# top.net
KiCad netlist of a schematic drawn in EAGLE
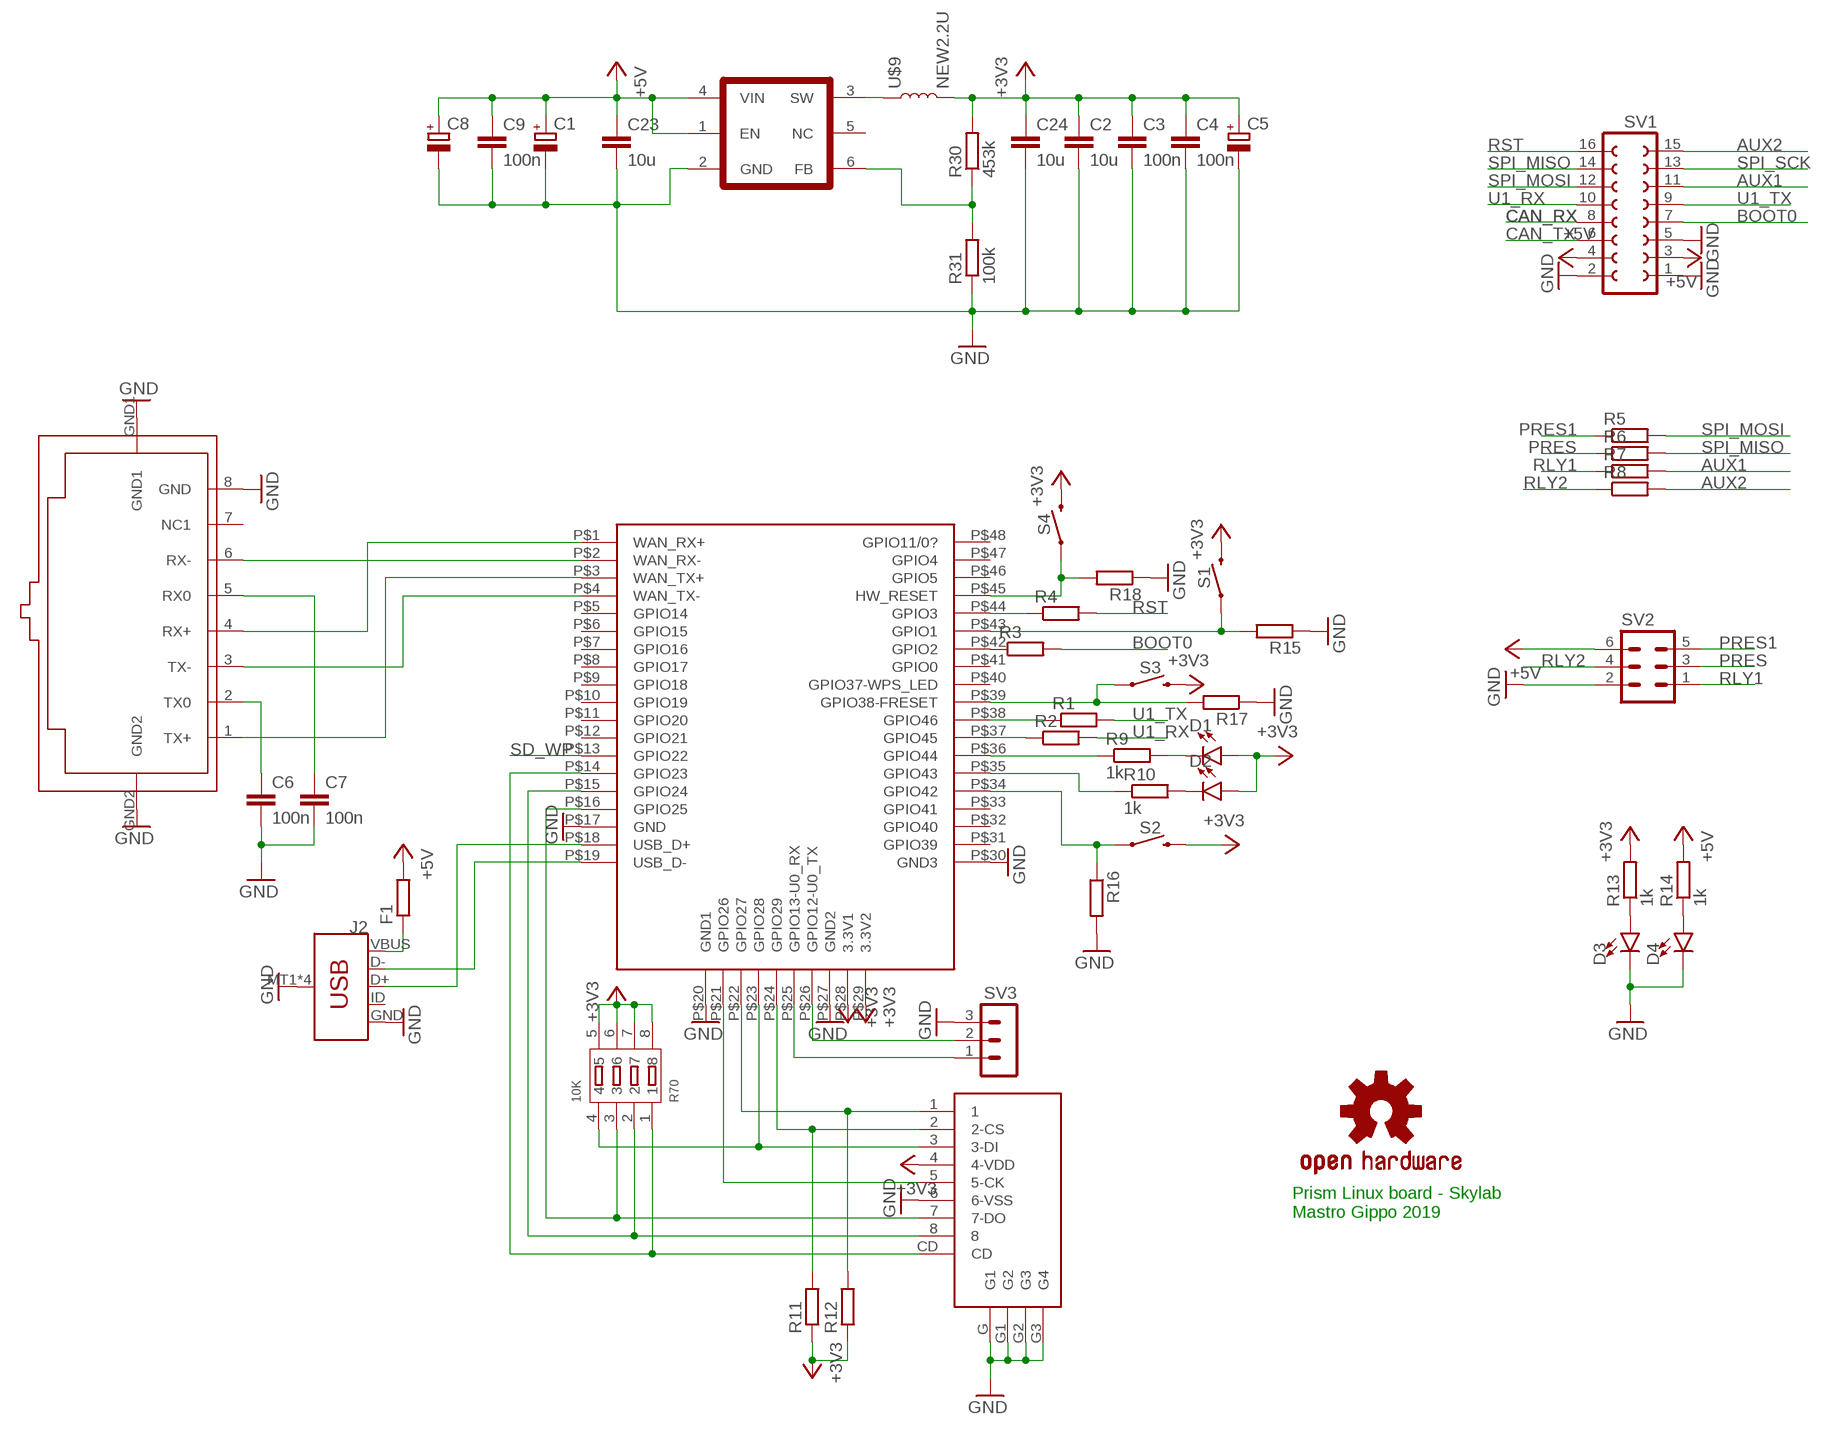
[diagram p0: schematic, sheet 1]

(export (version "E")
  (design (tool "Eeschema 10.0.6"))
  (components
    (comp (ref "C1")
      (value "CPOL-EUB/3528-21R")
      (footprint "eagle-import:B_3528-21R")
      (libsource (lib "eagle-import") (part "CPOL-EUB/3528-21R"))
    )
    (comp (ref "C2")
      (value "10u")
      (footprint "eagle-import:C0805K")
      (libsource (lib "eagle-import") (part "C-EUC0805K"))
    )
    (comp (ref "C3")
      (value "100n")
      (footprint "eagle-import:C0805K")
      (libsource (lib "eagle-import") (part "C-EUC0805K"))
    )
    (comp (ref "C4")
      (value "100n")
      (footprint "eagle-import:C0805K")
      (libsource (lib "eagle-import") (part "C-EUC0805K"))
    )
    (comp (ref "C5")
      (value "CPOL-EUB/3528-21R")
      (footprint "eagle-import:B_3528-21R")
      (libsource (lib "eagle-import") (part "CPOL-EUB/3528-21R"))
    )
    (comp (ref "C6")
      (value "100n")
      (footprint "eagle-import:C0805K")
      (libsource (lib "eagle-import") (part "C-EUC0805K"))
    )
    (comp (ref "C7")
      (value "100n")
      (footprint "eagle-import:C0805K")
      (libsource (lib "eagle-import") (part "C-EUC0805K"))
    )
    (comp (ref "C8")
      (value "CPOL-EUB/3528-21R")
      (footprint "eagle-import:B_3528-21R")
      (libsource (lib "eagle-import") (part "CPOL-EUB/3528-21R"))
    )
    (comp (ref "C9")
      (value "100n")
      (footprint "eagle-import:C0805K")
      (libsource (lib "eagle-import") (part "C-EUC0805K"))
    )
    (comp (ref "C23")
      (value "10u")
      (footprint "eagle-import:C0805K")
      (libsource (lib "eagle-import") (part "C-EUC0805K"))
    )
    (comp (ref "C24")
      (value "10u")
      (footprint "eagle-import:C0805K")
      (libsource (lib "eagle-import") (part "C-EUC0805K"))
    )
    (comp (ref "D1")
      (value "LED3MM")
      (footprint "eagle-import:LED_3MM")
      (libsource (lib "eagle-import") (part "LED3MM"))
    )
    (comp (ref "D2")
      (value "LED3MM")
      (footprint "eagle-import:LED_3MM")
      (libsource (lib "eagle-import") (part "LED3MM"))
    )
    (comp (ref "D3")
      (value "LED1206")
      (footprint "eagle-import:LED-1206")
      (libsource (lib "eagle-import") (part "LED1206"))
    )
    (comp (ref "D4")
      (value "LED1206")
      (footprint "eagle-import:LED-1206")
      (libsource (lib "eagle-import") (part "LED1206"))
    )
    (comp (ref "F1")
      (value "R-EU_R0603")
      (footprint "eagle-import:R0603")
      (libsource (lib "eagle-import") (part "R-EU_R0603"))
    )
    (comp (ref "J2")
      (value "USB_MICRO-B_SMT")
      (footprint "eagle-import:USB-MICROB")
      (libsource (lib "eagle-import") (part "USB_MICRO-B_SMT"))
    )
    (comp (ref "R1")
      (value "R-EU_R0805")
      (footprint "eagle-import:R0805")
      (libsource (lib "eagle-import") (part "R-EU_R0805"))
    )
    (comp (ref "R2")
      (value "R-EU_R0805")
      (footprint "eagle-import:R0805")
      (libsource (lib "eagle-import") (part "R-EU_R0805"))
    )
    (comp (ref "R3")
      (value "R-EU_R0805")
      (footprint "eagle-import:R0805")
      (libsource (lib "eagle-import") (part "R-EU_R0805"))
    )
    (comp (ref "R4")
      (value "R-EU_R0805")
      (footprint "eagle-import:R0805")
      (libsource (lib "eagle-import") (part "R-EU_R0805"))
    )
    (comp (ref "R5")
      (value "R-EU_R0805")
      (footprint "eagle-import:R0805")
      (libsource (lib "eagle-import") (part "R-EU_R0805"))
    )
    (comp (ref "R6")
      (value "R-EU_R0805")
      (footprint "eagle-import:R0805")
      (libsource (lib "eagle-import") (part "R-EU_R0805"))
    )
    (comp (ref "R7")
      (value "R-EU_R0805")
      (footprint "eagle-import:R0805")
      (libsource (lib "eagle-import") (part "R-EU_R0805"))
    )
    (comp (ref "R8")
      (value "R-EU_R0805")
      (footprint "eagle-import:R0805")
      (libsource (lib "eagle-import") (part "R-EU_R0805"))
    )
    (comp (ref "R9")
      (value "1k")
      (footprint "eagle-import:R0805")
      (libsource (lib "eagle-import") (part "R-EU_R0805"))
    )
    (comp (ref "R10")
      (value "1k")
      (footprint "eagle-import:R0805")
      (libsource (lib "eagle-import") (part "R-EU_R0805"))
    )
    (comp (ref "R11")
      (value "R-EU_R0805")
      (footprint "eagle-import:R0805")
      (libsource (lib "eagle-import") (part "R-EU_R0805"))
    )
    (comp (ref "R12")
      (value "R-EU_R0805")
      (footprint "eagle-import:R0805")
      (libsource (lib "eagle-import") (part "R-EU_R0805"))
    )
    (comp (ref "R13")
      (value "1k")
      (footprint "eagle-import:R0805")
      (libsource (lib "eagle-import") (part "R-EU_R0805"))
    )
    (comp (ref "R14")
      (value "1k")
      (footprint "eagle-import:R0805")
      (libsource (lib "eagle-import") (part "R-EU_R0805"))
    )
    (comp (ref "R15")
      (value "R-EU_R0805")
      (footprint "eagle-import:R0805")
      (libsource (lib "eagle-import") (part "R-EU_R0805"))
    )
    (comp (ref "R16")
      (value "R-EU_R0805")
      (footprint "eagle-import:R0805")
      (libsource (lib "eagle-import") (part "R-EU_R0805"))
    )
    (comp (ref "R17")
      (value "R-EU_R0805")
      (footprint "eagle-import:R0805")
      (libsource (lib "eagle-import") (part "R-EU_R0805"))
    )
    (comp (ref "R18")
      (value "R-EU_R0805")
      (footprint "eagle-import:R0805")
      (libsource (lib "eagle-import") (part "R-EU_R0805"))
    )
    (comp (ref "R30")
      (value "453k")
      (footprint "eagle-import:R0805")
      (libsource (lib "eagle-import") (part "R_EU"))
    )
    (comp (ref "R31")
      (value "100k")
      (footprint "eagle-import:R0805")
      (libsource (lib "eagle-import") (part "R_EU"))
    )
    (comp (ref "R70")
      (value "10K")
      (footprint "eagle-import:RA1206-8")
      (fields (field (name "MPN") "Chip-Array-Series-1%"))
      (libsource (lib "eagle-import") (part "SMD-RES-ARRAY-1K-4R(RA1206-8)"))
    )
    (comp (ref "S1")
      (value "MOMENTARY-SWITCH-SPST-SMD-6.0X3.5MM")
      (footprint "eagle-import:TACTILE_SWITCH_SMD_6.0X3.5MM")
      (libsource (lib "eagle-import") (part "MOMENTARY-SWITCH-SPST-SMD-6.0X3.5MM"))
    )
    (comp (ref "S2")
      (value "MOMENTARY-SWITCH-SPST-SMD-6.0X3.5MM")
      (footprint "eagle-import:TACTILE_SWITCH_SMD_6.0X3.5MM")
      (libsource (lib "eagle-import") (part "MOMENTARY-SWITCH-SPST-SMD-6.0X3.5MM"))
    )
    (comp (ref "S3")
      (value "MOMENTARY-SWITCH-SPST-PTH-RIGHT-ANGLE")
      (footprint "eagle-import:TACTILE_SWITCH_PTH_RIGHT_ANGLE")
      (libsource (lib "eagle-import") (part "MOMENTARY-SWITCH-SPST-PTH-RIGHT-ANGLE"))
    )
    (comp (ref "S4")
      (value "MOMENTARY-SWITCH-SPST-SMD-6.0X3.5MM")
      (footprint "eagle-import:TACTILE_SWITCH_SMD_6.0X3.5MM")
      (libsource (lib "eagle-import") (part "MOMENTARY-SWITCH-SPST-SMD-6.0X3.5MM"))
    )
    (comp (ref "SV1")
      (value "FE08-2")
      (footprint "eagle-import:FE08-2")
      (libsource (lib "eagle-import") (part "FE08-2"))
    )
    (comp (ref "SV2")
      (value "MA03-2")
      (footprint "eagle-import:MA03-2")
      (libsource (lib "eagle-import") (part "MA03-2"))
    )
    (comp (ref "SV3")
      (value "MA03-1")
      (footprint "eagle-import:MA03-1")
      (libsource (lib "eagle-import") (part "MA03-1"))
    )
    (comp (ref "U$1")
      (value "RJ45-TRAFO")
      (footprint "eagle-import:RJ45-TRAFO")
      (libsource (lib "eagle-import") (part "RJ45-TRAFO"))
    )
    (comp (ref "U$2")
      (value "SKW92B")
      (footprint "eagle-import:SKW92")
      (libsource (lib "eagle-import") (part "SKW92B"))
    )
    (comp (ref "U$3")
      (value "MICRO_SD")
      (footprint "eagle-import:MICRO_SD_C")
      (libsource (lib "eagle-import") (part "MICRO_SD"))
    )
    (comp (ref "U$4")
      (value "OSHW-LOGOS")
      (footprint "eagle-import:OSHW-LOGO-S")
      (libsource (lib "eagle-import") (part "OSHW-LOGOS"))
    )
    (comp (ref "U$8")
      (value "TLV62658")
      (footprint "eagle-import:SOT23-6")
      (libsource (lib "eagle-import") (part "TLV62658"))
    )
    (comp (ref "U$9")
      (value "NEW2.2U")
      (footprint "eagle-import:INDUCTOR_4X4MM")
      (libsource (lib "eagle-import") (part "NEW2.2U"))
    )
  )
  (nets
    (net (code "1") (name "+3V3") (class "Default")
      (node (ref "C2") (pin "1") (pinfunction "1_1") (pintype "passive"))
      (node (ref "C24") (pin "1") (pinfunction "1_1") (pintype "passive"))
      (node (ref "C3") (pin "1") (pinfunction "1_1") (pintype "passive"))
      (node (ref "C4") (pin "1") (pinfunction "1_1") (pintype "passive"))
      (node (ref "C5") (pin "+") (pinfunction "+_+") (pintype "passive"))
      (node (ref "D1") (pin "A") (pinfunction "A_A") (pintype "passive"))
      (node (ref "D2") (pin "A") (pinfunction "A_A") (pintype "passive"))
      (node (ref "R11") (pin "1") (pinfunction "1_1") (pintype "passive"))
      (node (ref "R12") (pin "1") (pinfunction "1_1") (pintype "passive"))
      (node (ref "R13") (pin "2") (pinfunction "2_2") (pintype "passive"))
      (node (ref "R30") (pin "2") (pinfunction "2_2") (pintype "passive"))
      (node (ref "R70") (pin "5") (pinfunction "5_5") (pintype "bidirectional"))
      (node (ref "R70") (pin "6") (pinfunction "6_6") (pintype "bidirectional"))
      (node (ref "R70") (pin "7") (pinfunction "7_7") (pintype "bidirectional"))
      (node (ref "R70") (pin "8") (pinfunction "8_8") (pintype "bidirectional"))
      (node (ref "S1") (pin "2") (pinfunction "2_2") (pintype "passive"))
      (node (ref "S2") (pin "2") (pinfunction "2_2") (pintype "passive"))
      (node (ref "S3") (pin "2") (pinfunction "2_2") (pintype "passive"))
      (node (ref "S4") (pin "2") (pinfunction "2_2") (pintype "passive"))
      (node (ref "U$2") (pin "P$28") (pinfunction "3.3V1_P$28") (pintype "bidirectional"))
      (node (ref "U$2") (pin "P$29") (pinfunction "3.3V2_P$29") (pintype "bidirectional"))
      (node (ref "U$3") (pin "4") (pinfunction "4-VDD_4") (pintype "bidirectional"))
      (node (ref "U$9") (pin "P$2") (pinfunction "2_P$2") (pintype "passive"))
    )
    (net (code "2") (name "+5V") (class "Default")
      (node (ref "C1") (pin "+") (pinfunction "+_+") (pintype "passive"))
      (node (ref "C23") (pin "1") (pinfunction "1_1") (pintype "passive"))
      (node (ref "C8") (pin "+") (pinfunction "+_+") (pintype "passive"))
      (node (ref "C9") (pin "1") (pinfunction "1_1") (pintype "passive"))
      (node (ref "F1") (pin "2") (pinfunction "2_2") (pintype "passive"))
      (node (ref "R14") (pin "2") (pinfunction "2_2") (pintype "passive"))
      (node (ref "SV1") (pin "3") (pinfunction "3_3") (pintype "passive"))
      (node (ref "SV1") (pin "4") (pinfunction "4_4") (pintype "passive"))
      (node (ref "SV2") (pin "6") (pinfunction "6_6") (pintype "passive"))
      (node (ref "U$8") (pin "1") (pinfunction "EN_1") (pintype "bidirectional"))
      (node (ref "U$8") (pin "4") (pinfunction "VIN_4") (pintype "bidirectional"))
    )
    (net (code "3") (name "/AUX1") (class "Default")
      (node (ref "R7") (pin "2") (pinfunction "2_2") (pintype "passive"))
      (node (ref "SV1") (pin "11") (pinfunction "11_11") (pintype "passive"))
    )
    (net (code "4") (name "/AUX2") (class "Default")
      (node (ref "R8") (pin "2") (pinfunction "2_2") (pintype "passive"))
      (node (ref "SV1") (pin "15") (pinfunction "15_15") (pintype "passive"))
    )
    (net (code "5") (name "/BOOT0") (class "Default")
      (node (ref "R3") (pin "2") (pinfunction "2_2") (pintype "passive"))
      (node (ref "SV1") (pin "7") (pinfunction "7_7") (pintype "passive"))
    )
    (net (code "6") (name "/CAN_RX") (class "Default")
      (node (ref "SV1") (pin "8") (pinfunction "8_8") (pintype "passive"))
    )
    (net (code "7") (name "/CAN_TX") (class "Default")
      (node (ref "SV1") (pin "6") (pinfunction "6_6") (pintype "passive"))
    )
    (net (code "8") (name "/PRES") (class "Default")
      (node (ref "R6") (pin "1") (pinfunction "1_1") (pintype "passive"))
      (node (ref "SV2") (pin "3") (pinfunction "3_3") (pintype "passive"))
    )
    (net (code "9") (name "/PRES1") (class "Default")
      (node (ref "R5") (pin "1") (pinfunction "1_1") (pintype "passive"))
      (node (ref "SV2") (pin "5") (pinfunction "5_5") (pintype "passive"))
    )
    (net (code "10") (name "/RLY1") (class "Default")
      (node (ref "R7") (pin "1") (pinfunction "1_1") (pintype "passive"))
      (node (ref "SV2") (pin "1") (pinfunction "1_1") (pintype "passive"))
    )
    (net (code "11") (name "/RLY2") (class "Default")
      (node (ref "R8") (pin "1") (pinfunction "1_1") (pintype "passive"))
      (node (ref "SV2") (pin "4") (pinfunction "4_4") (pintype "passive"))
    )
    (net (code "12") (name "/RST") (class "Default")
      (node (ref "R4") (pin "2") (pinfunction "2_2") (pintype "passive"))
      (node (ref "SV1") (pin "16") (pinfunction "16_16") (pintype "passive"))
    )
    (net (code "13") (name "/SD_WP") (class "Default")
      (node (ref "U$2") (pin "P$13") (pinfunction "GPIO22_P$13") (pintype "bidirectional"))
    )
    (net (code "14") (name "/SPI_MISO") (class "Default")
      (node (ref "R6") (pin "2") (pinfunction "2_2") (pintype "passive"))
      (node (ref "SV1") (pin "14") (pinfunction "14_14") (pintype "passive"))
    )
    (net (code "15") (name "/SPI_MOSI") (class "Default")
      (node (ref "R5") (pin "2") (pinfunction "2_2") (pintype "passive"))
      (node (ref "SV1") (pin "12") (pinfunction "12_12") (pintype "passive"))
    )
    (net (code "16") (name "/SPI_SCK") (class "Default")
      (node (ref "SV1") (pin "13") (pinfunction "13_13") (pintype "passive"))
    )
    (net (code "17") (name "/U1_RX") (class "Default")
      (node (ref "R2") (pin "2") (pinfunction "2_2") (pintype "passive"))
      (node (ref "SV1") (pin "10") (pinfunction "10_10") (pintype "passive"))
    )
    (net (code "18") (name "/U1_TX") (class "Default")
      (node (ref "R1") (pin "2") (pinfunction "2_2") (pintype "passive"))
      (node (ref "SV1") (pin "9") (pinfunction "9_9") (pintype "passive"))
    )
    (net (code "19") (name "GND") (class "Default")
      (node (ref "C1") (pin "-") (pinfunction "-_-") (pintype "passive"))
      (node (ref "C2") (pin "2") (pinfunction "2_2") (pintype "passive"))
      (node (ref "C23") (pin "2") (pinfunction "2_2") (pintype "passive"))
      (node (ref "C24") (pin "2") (pinfunction "2_2") (pintype "passive"))
      (node (ref "C3") (pin "2") (pinfunction "2_2") (pintype "passive"))
      (node (ref "C4") (pin "2") (pinfunction "2_2") (pintype "passive"))
      (node (ref "C5") (pin "-") (pinfunction "-_-") (pintype "passive"))
      (node (ref "C6") (pin "2") (pinfunction "2_2") (pintype "passive"))
      (node (ref "C7") (pin "2") (pinfunction "2_2") (pintype "passive"))
      (node (ref "C8") (pin "-") (pinfunction "-_-") (pintype "passive"))
      (node (ref "C9") (pin "2") (pinfunction "2_2") (pintype "passive"))
      (node (ref "D3") (pin "C") (pinfunction "C_C") (pintype "passive"))
      (node (ref "D4") (pin "C") (pinfunction "C_C") (pintype "passive"))
      (node (ref "J2") (pin "GND") (pinfunction "GND_GND") (pintype "power_in"))
      (node (ref "J2") (pin "MT1") (pinfunction "SHIELD_MT1") (pintype "bidirectional"))
      (node (ref "J2") (pin "MT2") (pinfunction "SHIELD_MT2") (pintype "bidirectional"))
      (node (ref "J2") (pin "P$1") (pinfunction "SHIELD_P$1") (pintype "bidirectional"))
      (node (ref "J2") (pin "P$2") (pinfunction "SHIELD_P$2") (pintype "bidirectional"))
      (node (ref "R15") (pin "1") (pinfunction "1_1") (pintype "passive"))
      (node (ref "R16") (pin "2") (pinfunction "2_2") (pintype "passive"))
      (node (ref "R17") (pin "1") (pinfunction "1_1") (pintype "passive"))
      (node (ref "R18") (pin "1") (pinfunction "1_1") (pintype "passive"))
      (node (ref "R31") (pin "1") (pinfunction "1_1") (pintype "passive"))
      (node (ref "SV1") (pin "1") (pinfunction "1_1") (pintype "passive"))
      (node (ref "SV1") (pin "2") (pinfunction "2_2") (pintype "passive"))
      (node (ref "SV1") (pin "5") (pinfunction "5_5") (pintype "passive"))
      (node (ref "SV2") (pin "2") (pinfunction "2_2") (pintype "passive"))
      (node (ref "SV3") (pin "3") (pinfunction "3_3") (pintype "passive"))
      (node (ref "U$1") (pin "8") (pinfunction "GND_8") (pintype "power_in"))
      (node (ref "U$1") (pin "GND1") (pinfunction "GND1_GND1") (pintype "power_in"))
      (node (ref "U$1") (pin "GND2") (pinfunction "GND2_GND2") (pintype "power_in"))
      (node (ref "U$2") (pin "P$17") (pinfunction "GND_P$17") (pintype "bidirectional"))
      (node (ref "U$2") (pin "P$20") (pinfunction "GND1_P$20") (pintype "bidirectional"))
      (node (ref "U$2") (pin "P$27") (pinfunction "GND2_P$27") (pintype "bidirectional"))
      (node (ref "U$2") (pin "P$30") (pinfunction "GND3_P$30") (pintype "bidirectional"))
      (node (ref "U$3") (pin "6") (pinfunction "6-VSS_6") (pintype "bidirectional"))
      (node (ref "U$3") (pin "G") (pinfunction "G1_G") (pintype "bidirectional"))
      (node (ref "U$3") (pin "G1") (pinfunction "G2_G1") (pintype "bidirectional"))
      (node (ref "U$3") (pin "G2") (pinfunction "G3_G2") (pintype "bidirectional"))
      (node (ref "U$3") (pin "G3") (pinfunction "G4_G3") (pintype "bidirectional"))
      (node (ref "U$8") (pin "2") (pinfunction "GND_2") (pintype "bidirectional"))
    )
    (net (code "20") (name "Net-(D1-C)") (class "Default")
      (node (ref "D1") (pin "K") (pinfunction "C_K") (pintype "passive"))
      (node (ref "R9") (pin "2") (pinfunction "2_2") (pintype "passive"))
    )
    (net (code "21") (name "Net-(D2-C)") (class "Default")
      (node (ref "D2") (pin "K") (pinfunction "C_K") (pintype "passive"))
      (node (ref "R10") (pin "2") (pinfunction "2_2") (pintype "passive"))
    )
    (net (code "22") (name "Net-(D3-PadA)") (class "Default")
      (node (ref "D3") (pin "A") (pinfunction "A_A") (pintype "passive"))
      (node (ref "R13") (pin "1") (pinfunction "1_1") (pintype "passive"))
    )
    (net (code "23") (name "Net-(D4-PadA)") (class "Default")
      (node (ref "D4") (pin "A") (pinfunction "A_A") (pintype "passive"))
      (node (ref "R14") (pin "1") (pinfunction "1_1") (pintype "passive"))
    )
    (net (code "24") (name "Net-(F1-Pad1)") (class "Default")
      (node (ref "F1") (pin "1") (pinfunction "1_1") (pintype "passive"))
      (node (ref "J2") (pin "VBUS") (pinfunction "VBUS_VBUS") (pintype "power_in"))
    )
    (net (code "25") (name "Net-(U$1-RX+)") (class "Default")
      (node (ref "U$1") (pin "4") (pinfunction "RX+_4") (pintype "bidirectional"))
      (node (ref "U$2") (pin "P$1") (pinfunction "WAN_RX+_P$1") (pintype "bidirectional"))
    )
    (net (code "26") (name "Net-(U$1-RX-)") (class "Default")
      (node (ref "U$1") (pin "6") (pinfunction "RX-_6") (pintype "bidirectional"))
      (node (ref "U$2") (pin "P$2") (pinfunction "WAN_RX-_P$2") (pintype "bidirectional"))
    )
    (net (code "27") (name "Net-(U$1-RX0)") (class "Default")
      (node (ref "C7") (pin "1") (pinfunction "1_1") (pintype "passive"))
      (node (ref "U$1") (pin "5") (pinfunction "RX0_5") (pintype "bidirectional"))
    )
    (net (code "28") (name "Net-(U$1-TX+)") (class "Default")
      (node (ref "U$1") (pin "1") (pinfunction "TX+_1") (pintype "bidirectional"))
      (node (ref "U$2") (pin "P$3") (pinfunction "WAN_TX+_P$3") (pintype "bidirectional"))
    )
    (net (code "29") (name "Net-(U$1-TX-)") (class "Default")
      (node (ref "U$1") (pin "3") (pinfunction "TX-_3") (pintype "bidirectional"))
      (node (ref "U$2") (pin "P$4") (pinfunction "WAN_TX-_P$4") (pintype "bidirectional"))
    )
    (net (code "30") (name "Net-(U$1-TX0)") (class "Default")
      (node (ref "C6") (pin "1") (pinfunction "1_1") (pintype "passive"))
      (node (ref "U$1") (pin "2") (pinfunction "TX0_2") (pintype "bidirectional"))
    )
    (net (code "31") (name "Net-(U$2-GPIO1)") (class "Default")
      (node (ref "R15") (pin "2") (pinfunction "2_2") (pintype "passive"))
      (node (ref "S1") (pin "1") (pinfunction "1_1") (pintype "passive"))
      (node (ref "U$2") (pin "P$43") (pinfunction "GPIO1_P$43") (pintype "bidirectional"))
    )
    (net (code "32") (name "Net-(U$2-GPIO2)") (class "Default")
      (node (ref "R3") (pin "1") (pinfunction "1_1") (pintype "passive"))
      (node (ref "U$2") (pin "P$42") (pinfunction "GPIO2_P$42") (pintype "bidirectional"))
    )
    (net (code "33") (name "Net-(U$2-GPIO3)") (class "Default")
      (node (ref "R4") (pin "1") (pinfunction "1_1") (pintype "passive"))
      (node (ref "U$2") (pin "P$44") (pinfunction "GPIO3_P$44") (pintype "bidirectional"))
    )
    (net (code "34") (name "Net-(U$2-GPIO12-U0_TX)") (class "Default")
      (node (ref "SV3") (pin "2") (pinfunction "2_2") (pintype "passive"))
      (node (ref "U$2") (pin "P$26") (pinfunction "GPIO12-U0_TX_P$26") (pintype "bidirectional"))
    )
    (net (code "35") (name "Net-(U$2-GPIO13-U0_RX)") (class "Default")
      (node (ref "SV3") (pin "1") (pinfunction "1_1") (pintype "passive"))
      (node (ref "U$2") (pin "P$25") (pinfunction "GPIO13-U0_RX_P$25") (pintype "bidirectional"))
    )
    (net (code "36") (name "Net-(U$2-GPIO23)") (class "Default")
      (node (ref "R70") (pin "1") (pinfunction "1_1") (pintype "bidirectional"))
      (node (ref "U$2") (pin "P$14") (pinfunction "GPIO23_P$14") (pintype "bidirectional"))
      (node (ref "U$3") (pin "CD") (pinfunction "CD_CD") (pintype "bidirectional"))
    )
    (net (code "37") (name "Net-(U$2-GPIO24)") (class "Default")
      (node (ref "R70") (pin "2") (pinfunction "2_2") (pintype "bidirectional"))
      (node (ref "U$2") (pin "P$15") (pinfunction "GPIO24_P$15") (pintype "bidirectional"))
      (node (ref "U$3") (pin "8") (pinfunction "8_8") (pintype "bidirectional"))
    )
    (net (code "38") (name "Net-(U$2-GPIO25)") (class "Default")
      (node (ref "R70") (pin "3") (pinfunction "3_3") (pintype "bidirectional"))
      (node (ref "U$2") (pin "P$16") (pinfunction "GPIO25_P$16") (pintype "bidirectional"))
      (node (ref "U$3") (pin "7") (pinfunction "7-DO_7") (pintype "bidirectional"))
    )
    (net (code "39") (name "Net-(U$2-GPIO26)") (class "Default")
      (node (ref "U$2") (pin "P$21") (pinfunction "GPIO26_P$21") (pintype "bidirectional"))
      (node (ref "U$3") (pin "5") (pinfunction "5-CK_5") (pintype "bidirectional"))
    )
    (net (code "40") (name "Net-(U$2-GPIO27)") (class "Default")
      (node (ref "R12") (pin "2") (pinfunction "2_2") (pintype "passive"))
      (node (ref "U$2") (pin "P$22") (pinfunction "GPIO27_P$22") (pintype "bidirectional"))
      (node (ref "U$3") (pin "1") (pinfunction "1_1") (pintype "bidirectional"))
    )
    (net (code "41") (name "Net-(U$2-GPIO28)") (class "Default")
      (node (ref "R70") (pin "4") (pinfunction "4_4") (pintype "bidirectional"))
      (node (ref "U$2") (pin "P$23") (pinfunction "GPIO28_P$23") (pintype "bidirectional"))
      (node (ref "U$3") (pin "3") (pinfunction "3-DI_3") (pintype "bidirectional"))
    )
    (net (code "42") (name "Net-(U$2-GPIO29)") (class "Default")
      (node (ref "R11") (pin "2") (pinfunction "2_2") (pintype "passive"))
      (node (ref "U$2") (pin "P$24") (pinfunction "GPIO29_P$24") (pintype "bidirectional"))
      (node (ref "U$3") (pin "2") (pinfunction "2-CS_2") (pintype "bidirectional"))
    )
    (net (code "43") (name "Net-(U$2-GPIO38-FRESET)") (class "Default")
      (node (ref "R17") (pin "2") (pinfunction "2_2") (pintype "passive"))
      (node (ref "S3") (pin "1") (pinfunction "1_1") (pintype "passive"))
      (node (ref "U$2") (pin "P$39") (pinfunction "GPIO38-FRESET_P$39") (pintype "bidirectional"))
    )
    (net (code "44") (name "Net-(U$2-GPIO42)") (class "Default")
      (node (ref "R16") (pin "1") (pinfunction "1_1") (pintype "passive"))
      (node (ref "S2") (pin "1") (pinfunction "1_1") (pintype "passive"))
      (node (ref "U$2") (pin "P$34") (pinfunction "GPIO42_P$34") (pintype "bidirectional"))
    )
    (net (code "45") (name "Net-(U$2-GPIO43)") (class "Default")
      (node (ref "R10") (pin "1") (pinfunction "1_1") (pintype "passive"))
      (node (ref "U$2") (pin "P$35") (pinfunction "GPIO43_P$35") (pintype "bidirectional"))
    )
    (net (code "46") (name "Net-(U$2-GPIO44)") (class "Default")
      (node (ref "R9") (pin "1") (pinfunction "1_1") (pintype "passive"))
      (node (ref "U$2") (pin "P$36") (pinfunction "GPIO44_P$36") (pintype "bidirectional"))
    )
    (net (code "47") (name "Net-(U$2-GPIO45)") (class "Default")
      (node (ref "R2") (pin "1") (pinfunction "1_1") (pintype "passive"))
      (node (ref "U$2") (pin "P$37") (pinfunction "GPIO45_P$37") (pintype "bidirectional"))
    )
    (net (code "48") (name "Net-(U$2-GPIO46)") (class "Default")
      (node (ref "R1") (pin "1") (pinfunction "1_1") (pintype "passive"))
      (node (ref "U$2") (pin "P$38") (pinfunction "GPIO46_P$38") (pintype "bidirectional"))
    )
    (net (code "49") (name "Net-(U$2-HW_RESET)") (class "Default")
      (node (ref "R18") (pin "2") (pinfunction "2_2") (pintype "passive"))
      (node (ref "S4") (pin "1") (pinfunction "1_1") (pintype "passive"))
      (node (ref "U$2") (pin "P$45") (pinfunction "HW_RESET_P$45") (pintype "bidirectional"))
    )
    (net (code "50") (name "Net-(U$2-USB_D+)") (class "Default")
      (node (ref "J2") (pin "D+") (pinfunction "D+_D+") (pintype "bidirectional"))
      (node (ref "U$2") (pin "P$18") (pinfunction "USB_D+_P$18") (pintype "bidirectional"))
    )
    (net (code "51") (name "Net-(U$2-USB_D-)") (class "Default")
      (node (ref "J2") (pin "D-") (pinfunction "D-_D-") (pintype "bidirectional"))
      (node (ref "U$2") (pin "P$19") (pinfunction "USB_D-_P$19") (pintype "bidirectional"))
    )
    (net (code "52") (name "Net-(U$8-FB)") (class "Default")
      (node (ref "R30") (pin "1") (pinfunction "1_1") (pintype "passive"))
      (node (ref "R31") (pin "2") (pinfunction "2_2") (pintype "passive"))
      (node (ref "U$8") (pin "6") (pinfunction "FB_6") (pintype "bidirectional"))
    )
    (net (code "53") (name "Net-(U$8-SW)") (class "Default")
      (node (ref "U$8") (pin "3") (pinfunction "SW_3") (pintype "bidirectional"))
      (node (ref "U$9") (pin "P$1") (pinfunction "1_P$1") (pintype "passive"))
    )
    (net (code "54") (name "unconnected-(J2-PadID)") (class "Default")
      (node (ref "J2") (pin "ID") (pinfunction "ID_ID") (pintype "bidirectional"))
    )
    (net (code "55") (name "unconnected-(U$1-NC1-Pad7)") (class "Default")
      (node (ref "U$1") (pin "7") (pinfunction "NC1_7") (pintype "no_connect"))
    )
    (net (code "56") (name "unconnected-(U$2-GPIO0-PadP$41)") (class "Default")
      (node (ref "U$2") (pin "P$41") (pinfunction "GPIO0_P$41") (pintype "bidirectional"))
    )
    (net (code "57") (name "unconnected-(U$2-GPIO4-PadP$47)") (class "Default")
      (node (ref "U$2") (pin "P$47") (pinfunction "GPIO4_P$47") (pintype "bidirectional"))
    )
    (net (code "58") (name "unconnected-(U$2-GPIO5-PadP$46)") (class "Default")
      (node (ref "U$2") (pin "P$46") (pinfunction "GPIO5_P$46") (pintype "bidirectional"))
    )
    (net (code "59") (name "unconnected-(U$2-GPIO11{slash}0?-PadP$48)") (class "Default")
      (node (ref "U$2") (pin "P$48") (pinfunction "GPIO11/0?_P$48") (pintype "bidirectional"))
    )
    (net (code "60") (name "unconnected-(U$2-GPIO14-PadP$5)") (class "Default")
      (node (ref "U$2") (pin "P$5") (pinfunction "GPIO14_P$5") (pintype "bidirectional"))
    )
    (net (code "61") (name "unconnected-(U$2-GPIO15-PadP$6)") (class "Default")
      (node (ref "U$2") (pin "P$6") (pinfunction "GPIO15_P$6") (pintype "bidirectional"))
    )
    (net (code "62") (name "unconnected-(U$2-GPIO16-PadP$7)") (class "Default")
      (node (ref "U$2") (pin "P$7") (pinfunction "GPIO16_P$7") (pintype "bidirectional"))
    )
    (net (code "63") (name "unconnected-(U$2-GPIO17-PadP$8)") (class "Default")
      (node (ref "U$2") (pin "P$8") (pinfunction "GPIO17_P$8") (pintype "bidirectional"))
    )
    (net (code "64") (name "unconnected-(U$2-GPIO18-PadP$9)") (class "Default")
      (node (ref "U$2") (pin "P$9") (pinfunction "GPIO18_P$9") (pintype "bidirectional"))
    )
    (net (code "65") (name "unconnected-(U$2-GPIO19-PadP$10)") (class "Default")
      (node (ref "U$2") (pin "P$10") (pinfunction "GPIO19_P$10") (pintype "bidirectional"))
    )
    (net (code "66") (name "unconnected-(U$2-GPIO20-PadP$11)") (class "Default")
      (node (ref "U$2") (pin "P$11") (pinfunction "GPIO20_P$11") (pintype "bidirectional"))
    )
    (net (code "67") (name "unconnected-(U$2-GPIO21-PadP$12)") (class "Default")
      (node (ref "U$2") (pin "P$12") (pinfunction "GPIO21_P$12") (pintype "bidirectional"))
    )
    (net (code "68") (name "unconnected-(U$2-GPIO37-WPS_LED-PadP$40)") (class "Default")
      (node (ref "U$2") (pin "P$40") (pinfunction "GPIO37-WPS_LED_P$40") (pintype "bidirectional"))
    )
    (net (code "69") (name "unconnected-(U$2-GPIO39-PadP$31)") (class "Default")
      (node (ref "U$2") (pin "P$31") (pinfunction "GPIO39_P$31") (pintype "bidirectional"))
    )
    (net (code "70") (name "unconnected-(U$2-GPIO40-PadP$32)") (class "Default")
      (node (ref "U$2") (pin "P$32") (pinfunction "GPIO40_P$32") (pintype "bidirectional"))
    )
    (net (code "71") (name "unconnected-(U$2-GPIO41-PadP$33)") (class "Default")
      (node (ref "U$2") (pin "P$33") (pinfunction "GPIO41_P$33") (pintype "bidirectional"))
    )
    (net (code "72") (name "unconnected-(U$8-NC-Pad5)") (class "Default")
      (node (ref "U$8") (pin "5") (pinfunction "NC_5") (pintype "bidirectional"))
    )
  )
)
